# connector_boards.net
KiCad netlist of a schematic drawn in Altium Designer
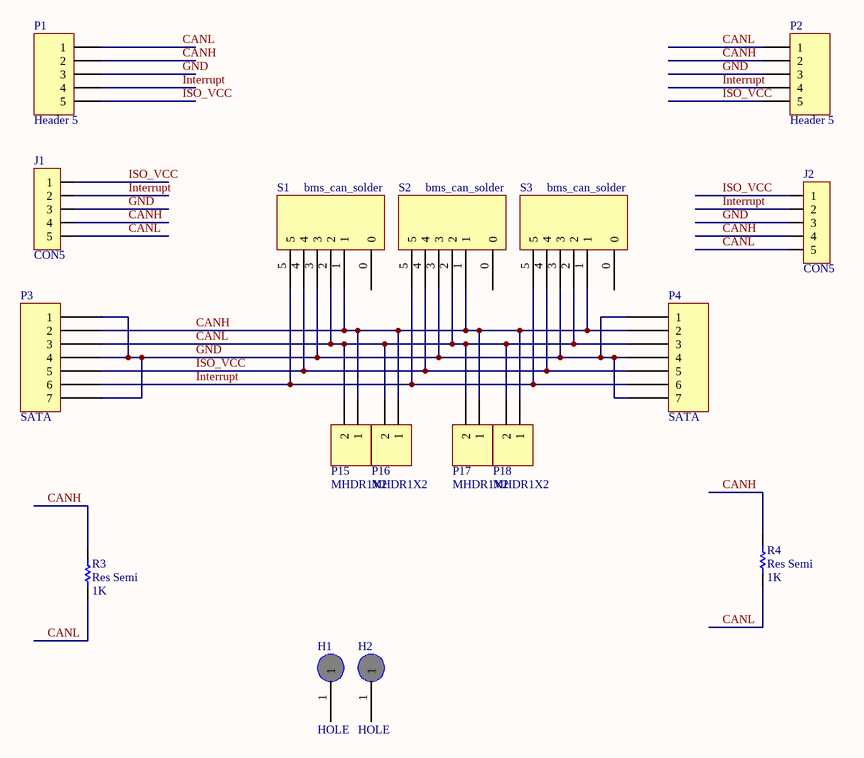
[diagram p0: connector_boards.SchDoc]

(export (version "E")
  (design (tool "Eeschema 10.0.6"))
  (components
    (comp (ref "H1")
      (value "HOLE")
      (footprint "M2.5")
      (description "Hole")
      (libsource (lib "Miscellaneous") (part "HOLE"))
    )
    (comp (ref "H2")
      (value "HOLE")
      (footprint "M2.5")
      (description "Hole")
      (libsource (lib "Miscellaneous") (part "HOLE"))
    )
    (comp (ref "J1")
      (value "CON5")
      (footprint "TRIAD5F")
      (description "Connector")
      (libsource (lib "") (part "CON5_1"))
    )
    (comp (ref "J2")
      (value "CON5")
      (footprint "TRIAD5F")
      (description "Connector")
      (libsource (lib "Connectors") (part "CON5"))
    )
    (comp (ref "P1")
      (value "Header 5")
      (footprint "HDR1X5")
      (description "Header, 5-Pin")
      (fields (field (name "PUBLISHER") "Altium Limited"))
      (libsource (lib "Miscellaneous Connectors") (part "Header 5"))
    )
    (comp (ref "P2")
      (value "Header 5")
      (footprint "HDR1X5")
      (description "Header, 5-Pin")
      (fields (field (name "PUBLISHER") "Altium Limited"))
      (libsource (lib "") (part "Header 5_1"))
    )
    (comp (ref "P3") (value "SATA") (footprint "47080-4005-SATA") (libsource (lib "BMS") (part "SATA")))
    (comp (ref "P4") (value "SATA") (footprint "47080-4005-SATA") (libsource (lib "") (part "SATA_1")))
    (comp (ref "P15")
      (value "MHDR1X2")
      (footprint "MHDR1X2")
      (description "Header, 2-Pin")
      (fields (field (name "PUBLISHER") "Altium Limited"))
      (libsource (lib "Miscellaneous Connectors") (part "MHDR1X2"))
    )
    (comp (ref "P16")
      (value "MHDR1X2")
      (footprint "MHDR1X2")
      (description "Header, 2-Pin")
      (fields (field (name "PUBLISHER") "Altium Limited"))
      (libsource (lib "Miscellaneous Connectors") (part "MHDR1X2"))
    )
    (comp (ref "P17")
      (value "MHDR1X2")
      (footprint "MHDR1X2")
      (description "Header, 2-Pin")
      (fields (field (name "PUBLISHER") "Altium Limited"))
      (libsource (lib "Miscellaneous Connectors") (part "MHDR1X2"))
    )
    (comp (ref "P18")
      (value "MHDR1X2")
      (footprint "MHDR1X2")
      (description "Header, 2-Pin")
      (fields (field (name "PUBLISHER") "Altium Limited"))
      (libsource (lib "Miscellaneous Connectors") (part "MHDR1X2"))
    )
    (comp (ref "R3")
      (value "Res Semi")
      (footprint "1005[0402]")
      (description "Semiconductor Resistor")
      (fields (field (name "ALTIUM_VALUE") "1K") (field (name "PUBLISHER") "Altium Limited"))
      (libsource (lib "Miscellaneous Devices") (part "Res Semi"))
    )
    (comp (ref "R4")
      (value "Res Semi")
      (footprint "1005[0402]")
      (description "Semiconductor Resistor")
      (fields (field (name "ALTIUM_VALUE") "1K") (field (name "PUBLISHER") "Altium Limited"))
      (libsource (lib "Miscellaneous Devices") (part "Res Semi"))
    )
    (comp (ref "S1")
      (value "bms_can_solder")
      (footprint "pcb_bcan_soldertabs")
      (libsource (lib "BMS") (part "bms_can_solder"))
    )
    (comp (ref "S2")
      (value "bms_can_solder")
      (footprint "pcb_bcan_soldertabs")
      (libsource (lib "BMS") (part "bms_can_solder"))
    )
    (comp (ref "S3")
      (value "bms_can_solder")
      (footprint "pcb_bcan_soldertabs")
      (libsource (lib "BMS") (part "bms_can_solder"))
    )
  )
  (nets
    (net (code "1") (name "/CANH") (class "Default")
      (node (ref "J1") (pin "4") (pinfunction "4_4") (pintype "passive"))
      (node (ref "J2") (pin "4") (pinfunction "4_4") (pintype "passive"))
      (node (ref "P1") (pin "2") (pinfunction "2_2") (pintype "passive"))
      (node (ref "P15") (pin "1") (pinfunction "1_1") (pintype "passive"))
      (node (ref "P16") (pin "1") (pinfunction "1_1") (pintype "passive"))
      (node (ref "P17") (pin "1") (pinfunction "1_1") (pintype "passive"))
      (node (ref "P18") (pin "1") (pinfunction "1_1") (pintype "passive"))
      (node (ref "P2") (pin "2") (pinfunction "2_2") (pintype "passive"))
      (node (ref "P3") (pin "2") (pinfunction "2_2") (pintype "passive"))
      (node (ref "P4") (pin "2") (pinfunction "2_2") (pintype "passive"))
      (node (ref "R3") (pin "2") (pinfunction "2_2") (pintype "passive"))
      (node (ref "R4") (pin "2") (pinfunction "2_2") (pintype "passive"))
      (node (ref "S1") (pin "1") (pinfunction "1_1") (pintype "passive"))
      (node (ref "S2") (pin "1") (pinfunction "1_1") (pintype "passive"))
      (node (ref "S3") (pin "1") (pinfunction "1_1") (pintype "passive"))
    )
    (net (code "2") (name "/CANL") (class "Default")
      (node (ref "J1") (pin "5") (pinfunction "5_5") (pintype "passive"))
      (node (ref "J2") (pin "5") (pinfunction "5_5") (pintype "passive"))
      (node (ref "P1") (pin "1") (pinfunction "1_1") (pintype "passive"))
      (node (ref "P15") (pin "2") (pinfunction "2_2") (pintype "passive"))
      (node (ref "P16") (pin "2") (pinfunction "2_2") (pintype "passive"))
      (node (ref "P17") (pin "2") (pinfunction "2_2") (pintype "passive"))
      (node (ref "P18") (pin "2") (pinfunction "2_2") (pintype "passive"))
      (node (ref "P2") (pin "1") (pinfunction "1_1") (pintype "passive"))
      (node (ref "P3") (pin "3") (pinfunction "3_3") (pintype "passive"))
      (node (ref "P4") (pin "3") (pinfunction "3_3") (pintype "passive"))
      (node (ref "R3") (pin "1") (pinfunction "1_1") (pintype "passive"))
      (node (ref "R4") (pin "1") (pinfunction "1_1") (pintype "passive"))
      (node (ref "S1") (pin "2") (pinfunction "2_2") (pintype "passive"))
      (node (ref "S2") (pin "2") (pinfunction "2_2") (pintype "passive"))
      (node (ref "S3") (pin "2") (pinfunction "2_2") (pintype "passive"))
    )
    (net (code "3") (name "/GND") (class "Default")
      (node (ref "J1") (pin "3") (pinfunction "3_3") (pintype "passive"))
      (node (ref "J2") (pin "3") (pinfunction "3_3") (pintype "passive"))
      (node (ref "P1") (pin "3") (pinfunction "3_3") (pintype "passive"))
      (node (ref "P2") (pin "3") (pinfunction "3_3") (pintype "passive"))
      (node (ref "P3") (pin "1") (pinfunction "1_1") (pintype "passive"))
      (node (ref "P3") (pin "4") (pinfunction "4_4") (pintype "passive"))
      (node (ref "P3") (pin "7") (pinfunction "7_7") (pintype "passive"))
      (node (ref "P4") (pin "1") (pinfunction "1_1") (pintype "passive"))
      (node (ref "P4") (pin "4") (pinfunction "4_4") (pintype "passive"))
      (node (ref "P4") (pin "7") (pinfunction "7_7") (pintype "passive"))
      (node (ref "S1") (pin "3") (pinfunction "3_3") (pintype "passive"))
      (node (ref "S2") (pin "3") (pinfunction "3_3") (pintype "passive"))
      (node (ref "S3") (pin "3") (pinfunction "3_3") (pintype "passive"))
    )
    (net (code "4") (name "/ISO_VCC") (class "Default")
      (node (ref "J1") (pin "1") (pinfunction "1_1") (pintype "passive"))
      (node (ref "J2") (pin "1") (pinfunction "1_1") (pintype "passive"))
      (node (ref "P1") (pin "5") (pinfunction "5_5") (pintype "passive"))
      (node (ref "P2") (pin "5") (pinfunction "5_5") (pintype "passive"))
      (node (ref "P3") (pin "5") (pinfunction "5_5") (pintype "passive"))
      (node (ref "P4") (pin "5") (pinfunction "5_5") (pintype "passive"))
      (node (ref "S1") (pin "4") (pinfunction "4_4") (pintype "passive"))
      (node (ref "S2") (pin "4") (pinfunction "4_4") (pintype "passive"))
      (node (ref "S3") (pin "4") (pinfunction "4_4") (pintype "passive"))
    )
    (net (code "5") (name "/Interrupt") (class "Default")
      (node (ref "J1") (pin "2") (pinfunction "2_2") (pintype "passive"))
      (node (ref "J2") (pin "2") (pinfunction "2_2") (pintype "passive"))
      (node (ref "P1") (pin "4") (pinfunction "4_4") (pintype "passive"))
      (node (ref "P2") (pin "4") (pinfunction "4_4") (pintype "passive"))
      (node (ref "P3") (pin "6") (pinfunction "6_6") (pintype "passive"))
      (node (ref "P4") (pin "6") (pinfunction "6_6") (pintype "passive"))
      (node (ref "S1") (pin "5") (pinfunction "5_5") (pintype "passive"))
      (node (ref "S2") (pin "5") (pinfunction "5_5") (pintype "passive"))
      (node (ref "S3") (pin "5") (pinfunction "5_5") (pintype "passive"))
    )
    (net (code "6") (name "unconnected-(H1-Pad1)") (class "Default")
      (node (ref "H1") (pin "1") (pinfunction "1_1") (pintype "passive"))
    )
    (net (code "7") (name "unconnected-(H2-Pad1)") (class "Default")
      (node (ref "H2") (pin "1") (pinfunction "1_1") (pintype "passive"))
    )
    (net (code "8") (name "unconnected-(S1-Pad0)") (class "Default")
      (node (ref "S1") (pin "0") (pinfunction "0_0") (pintype "passive"))
    )
    (net (code "9") (name "unconnected-(S2-Pad0)") (class "Default")
      (node (ref "S2") (pin "0") (pinfunction "0_0") (pintype "passive"))
    )
    (net (code "10") (name "unconnected-(S3-Pad0)") (class "Default")
      (node (ref "S3") (pin "0") (pinfunction "0_0") (pintype "passive"))
    )
  )
)
